# boardShildSchematic.net
KiCad netlist of a schematic drawn in EAGLE
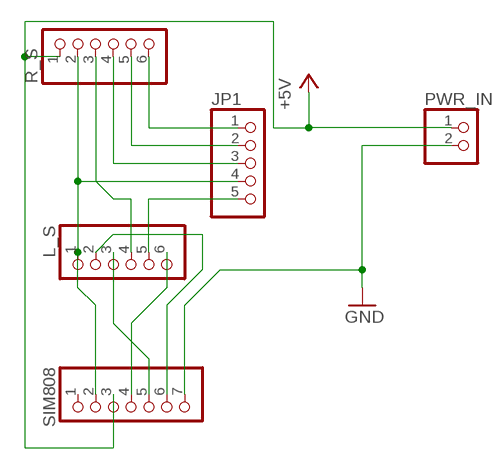
[diagram p0: schematic, sheet 1]

(export (version "E")
  (design (tool "Eeschema 10.0.6"))
  (components
    (comp (ref "JP1")
      (value "PINHD-1X5")
      (footprint "eagle-import:1X05")
      (libsource (lib "eagle-import") (part "PINHD-1X5"))
    )
    (comp (ref "L_S")
      (value "PINHD-1X6")
      (footprint "eagle-import:1X06")
      (libsource (lib "eagle-import") (part "PINHD-1X6"))
    )
    (comp (ref "PWR_IN")
      (value "PINHD-1X2")
      (footprint "eagle-import:1X02")
      (libsource (lib "eagle-import") (part "PINHD-1X2"))
    )
    (comp (ref "R_S")
      (value "PINHD-1X6")
      (footprint "eagle-import:1X06")
      (libsource (lib "eagle-import") (part "PINHD-1X6"))
    )
    (comp (ref "SIM808")
      (value "PINHD-1X7")
      (footprint "eagle-import:1X07")
      (libsource (lib "eagle-import") (part "PINHD-1X7"))
    )
  )
  (nets
    (net (code "1") (name "+5V") (class "Default")
      (node (ref "PWR_IN") (pin "1") (pinfunction "1_1") (pintype "passive"))
      (node (ref "R_S") (pin "1") (pinfunction "1_1") (pintype "passive"))
      (node (ref "SIM808") (pin "3") (pinfunction "3_3") (pintype "passive"))
    )
    (net (code "2") (name "GND") (class "Default")
      (node (ref "PWR_IN") (pin "2") (pinfunction "2_2") (pintype "passive"))
      (node (ref "SIM808") (pin "7") (pinfunction "7_7") (pintype "passive"))
    )
    (net (code "3") (name "Net-(JP1-Pad1)") (class "Default")
      (node (ref "JP1") (pin "1") (pinfunction "1_1") (pintype "passive"))
      (node (ref "R_S") (pin "6") (pinfunction "6_6") (pintype "passive"))
    )
    (net (code "4") (name "Net-(JP1-Pad2)") (class "Default")
      (node (ref "JP1") (pin "2") (pinfunction "2_2") (pintype "passive"))
      (node (ref "R_S") (pin "5") (pinfunction "5_5") (pintype "passive"))
    )
    (net (code "5") (name "Net-(JP1-Pad3)") (class "Default")
      (node (ref "JP1") (pin "3") (pinfunction "3_3") (pintype "passive"))
      (node (ref "R_S") (pin "4") (pinfunction "4_4") (pintype "passive"))
    )
    (net (code "6") (name "Net-(JP1-Pad4)") (class "Default")
      (node (ref "JP1") (pin "4") (pinfunction "4_4") (pintype "passive"))
      (node (ref "L_S") (pin "1") (pinfunction "1_1") (pintype "passive"))
      (node (ref "R_S") (pin "2") (pinfunction "2_2") (pintype "passive"))
      (node (ref "SIM808") (pin "2") (pinfunction "2_2") (pintype "passive"))
    )
    (net (code "7") (name "Net-(JP1-Pad5)") (class "Default")
      (node (ref "JP1") (pin "5") (pinfunction "5_5") (pintype "passive"))
      (node (ref "L_S") (pin "5") (pinfunction "5_5") (pintype "passive"))
    )
    (net (code "8") (name "Net-(L_S-Pad2)") (class "Default")
      (node (ref "L_S") (pin "2") (pinfunction "2_2") (pintype "passive"))
      (node (ref "SIM808") (pin "6") (pinfunction "6_6") (pintype "passive"))
    )
    (net (code "9") (name "Net-(L_S-Pad3)") (class "Default")
      (node (ref "L_S") (pin "3") (pinfunction "3_3") (pintype "passive"))
      (node (ref "SIM808") (pin "5") (pinfunction "5_5") (pintype "passive"))
    )
    (net (code "10") (name "Net-(L_S-Pad4)") (class "Default")
      (node (ref "L_S") (pin "4") (pinfunction "4_4") (pintype "passive"))
      (node (ref "R_S") (pin "3") (pinfunction "3_3") (pintype "passive"))
    )
    (net (code "11") (name "Net-(L_S-Pad6)") (class "Default")
      (node (ref "L_S") (pin "6") (pinfunction "6_6") (pintype "passive"))
      (node (ref "SIM808") (pin "4") (pinfunction "4_4") (pintype "passive"))
    )
    (net (code "12") (name "unconnected-(SIM808-Pad1)") (class "Default")
      (node (ref "SIM808") (pin "1") (pinfunction "1_1") (pintype "passive"))
    )
  )
)
